# 01_SERIALIZER_V1-0.net
KiCad netlist of a schematic drawn in Altium Designer
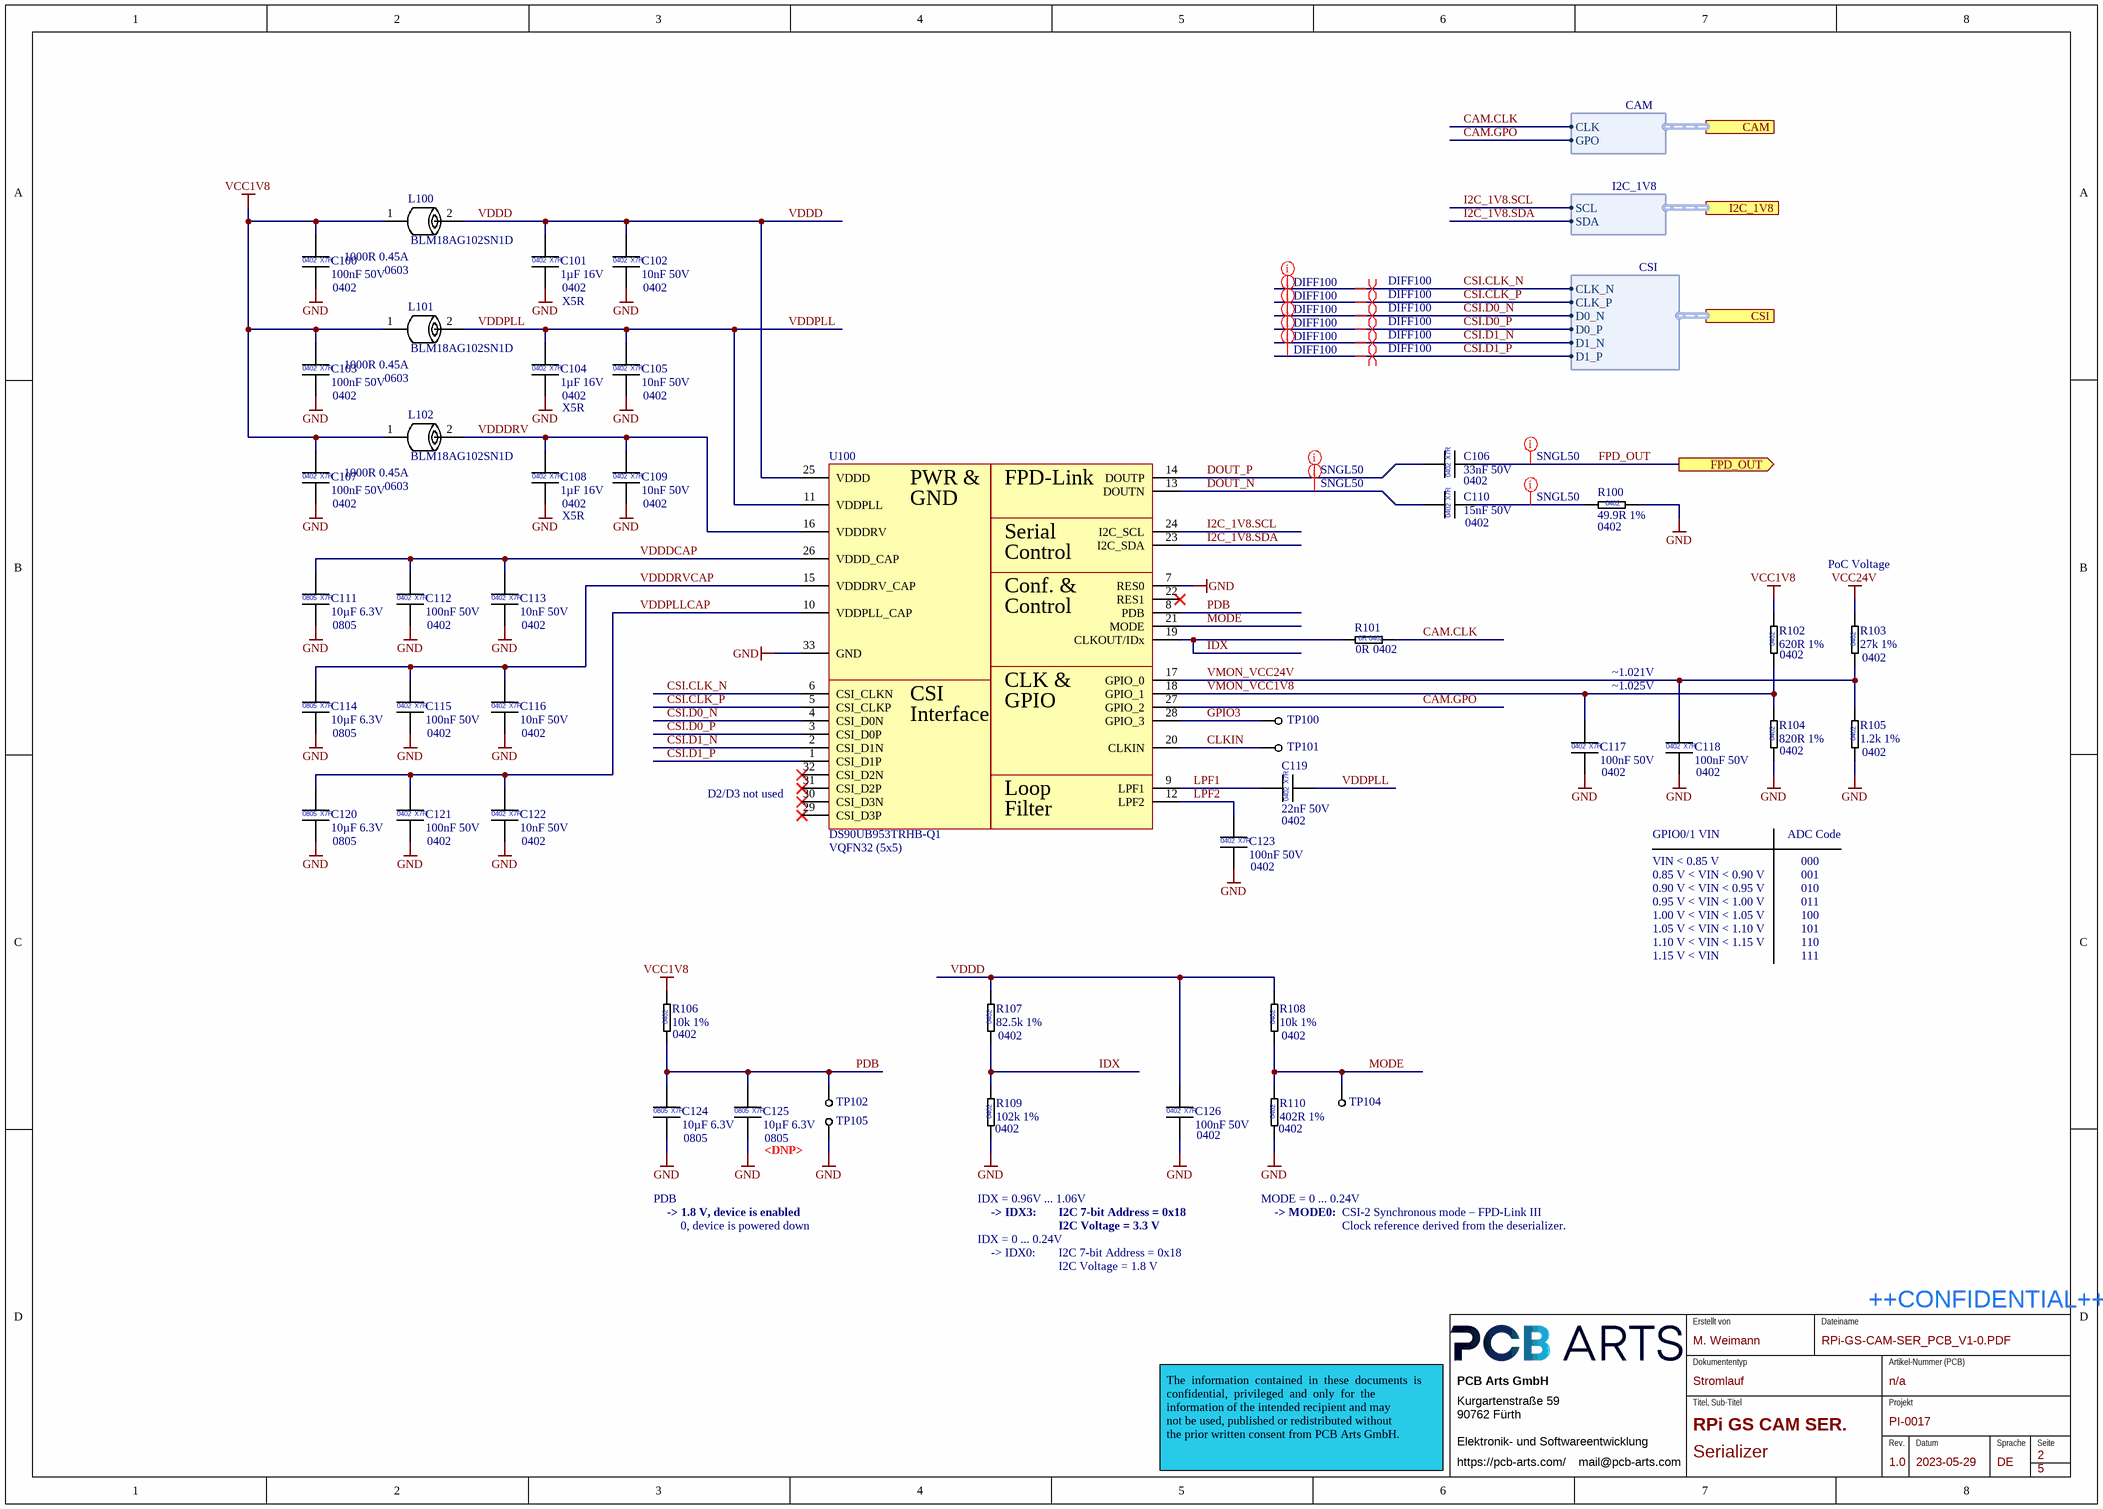
[diagram p0: 01_SERIALIZER_V1-0.SchDoc]

(export (version "E")
  (design (tool "Eeschema 10.0.6"))
  (components
    (comp (ref "C100")
      (value "100nF 50V")
      (footprint "Cap:CAP_0402_L")
      (description "Multilayer Ceramic Capacitors MLCC - SMD/SMT 0402 50VDC")
      (libsource (lib "Cap") (part "CAP_0402_100nF_50V"))
    )
    (comp (ref "C101")
      (value "1µF 16V")
      (footprint "Cap:CAP_0402_L")
      (description "Multilayer Ceramic Capacitors MLCC - SMD/SMT 0402 16VDC")
      (libsource (lib "Cap") (part "CAP_0402_1µF_16V"))
    )
    (comp (ref "C102")
      (value "10nF 50V")
      (footprint "Cap:CAP_0402_L")
      (description "Multilayer Ceramic Capacitors MLCC - SMD/SMT 0402 50VDC")
      (libsource (lib "Cap") (part "CAP_0402_10nF_50V"))
    )
    (comp (ref "C103")
      (value "100nF 50V")
      (footprint "Cap:CAP_0402_L")
      (description "Multilayer Ceramic Capacitors MLCC - SMD/SMT 0402 50VDC")
      (libsource (lib "Cap") (part "CAP_0402_100nF_50V"))
    )
    (comp (ref "C104")
      (value "1µF 16V")
      (footprint "Cap:CAP_0402_L")
      (description "Multilayer Ceramic Capacitors MLCC - SMD/SMT 0402 16VDC")
      (libsource (lib "Cap") (part "CAP_0402_1µF_16V"))
    )
    (comp (ref "C105")
      (value "10nF 50V")
      (footprint "Cap:CAP_0402_L")
      (description "Multilayer Ceramic Capacitors MLCC - SMD/SMT 0402 50VDC")
      (libsource (lib "Cap") (part "CAP_0402_10nF_50V"))
    )
    (comp (ref "C106")
      (value "33nF 50V")
      (footprint "Cap:CAP_0402_L")
      (description "Multilayer Ceramic Capacitors MLCC - SMD/SMT 0402 50VDC")
      (libsource (lib "Cap") (part "CAP_0402_33nF_50V"))
    )
    (comp (ref "C107")
      (value "100nF 50V")
      (footprint "Cap:CAP_0402_L")
      (description "Multilayer Ceramic Capacitors MLCC - SMD/SMT 0402 50VDC")
      (libsource (lib "Cap") (part "CAP_0402_100nF_50V"))
    )
    (comp (ref "C108")
      (value "1µF 16V")
      (footprint "Cap:CAP_0402_L")
      (description "Multilayer Ceramic Capacitors MLCC - SMD/SMT 0402 16VDC")
      (libsource (lib "Cap") (part "CAP_0402_1µF_16V"))
    )
    (comp (ref "C109")
      (value "10nF 50V")
      (footprint "Cap:CAP_0402_L")
      (description "Multilayer Ceramic Capacitors MLCC - SMD/SMT 0402 50VDC")
      (libsource (lib "Cap") (part "CAP_0402_10nF_50V"))
    )
    (comp (ref "C110")
      (value "15nF 50V")
      (footprint "Cap:CAP_0402_L")
      (description "Multilayer Ceramic Capacitors MLCC - SMD/SMT 0402 50VDC")
      (libsource (lib "Cap") (part "CAP_0402_15nF_50V"))
    )
    (comp (ref "C111")
      (value "10µF 6.3V")
      (footprint "Cap:CAP_0805")
      (description "Multilayer Ceramic Capacitors MLCC - SMD/SMT 10 uF 6.3 VDC 10% 0805 X7R")
      (libsource (lib "Cap") (part "CAP_0805_10µF_6.3V_X7R_10%"))
    )
    (comp (ref "C112")
      (value "100nF 50V")
      (footprint "Cap:CAP_0402_L")
      (description "Multilayer Ceramic Capacitors MLCC - SMD/SMT 0402 50VDC")
      (libsource (lib "Cap") (part "CAP_0402_100nF_50V"))
    )
    (comp (ref "C113")
      (value "10nF 50V")
      (footprint "Cap:CAP_0402_L")
      (description "Multilayer Ceramic Capacitors MLCC - SMD/SMT 0402 50VDC")
      (libsource (lib "Cap") (part "CAP_0402_10nF_50V"))
    )
    (comp (ref "C114")
      (value "10µF 6.3V")
      (footprint "Cap:CAP_0805")
      (description "Multilayer Ceramic Capacitors MLCC - SMD/SMT 10 uF 6.3 VDC 10% 0805 X7R")
      (libsource (lib "Cap") (part "CAP_0805_10µF_6.3V_X7R_10%"))
    )
    (comp (ref "C115")
      (value "100nF 50V")
      (footprint "Cap:CAP_0402_L")
      (description "Multilayer Ceramic Capacitors MLCC - SMD/SMT 0402 50VDC")
      (libsource (lib "Cap") (part "CAP_0402_100nF_50V"))
    )
    (comp (ref "C116")
      (value "10nF 50V")
      (footprint "Cap:CAP_0402_L")
      (description "Multilayer Ceramic Capacitors MLCC - SMD/SMT 0402 50VDC")
      (libsource (lib "Cap") (part "CAP_0402_10nF_50V"))
    )
    (comp (ref "C117")
      (value "100nF 50V")
      (footprint "Cap:CAP_0402_L")
      (description "Multilayer Ceramic Capacitors MLCC - SMD/SMT 0402 50VDC")
      (libsource (lib "Cap") (part "CAP_0402_100nF_50V"))
    )
    (comp (ref "C118")
      (value "100nF 50V")
      (footprint "Cap:CAP_0402_L")
      (description "Multilayer Ceramic Capacitors MLCC - SMD/SMT 0402 50VDC")
      (libsource (lib "Cap") (part "CAP_0402_100nF_50V"))
    )
    (comp (ref "C119")
      (value "22nF 50V")
      (footprint "Cap:CAP_0402_L")
      (description "Multilayer Ceramic Capacitors MLCC - SMD/SMT 0402 50VDC")
      (libsource (lib "Cap") (part "CAP_0402_22nF_50V"))
    )
    (comp (ref "C120")
      (value "10µF 6.3V")
      (footprint "Cap:CAP_0805")
      (description "Multilayer Ceramic Capacitors MLCC - SMD/SMT 10 uF 6.3 VDC 10% 0805 X7R")
      (libsource (lib "Cap") (part "CAP_0805_10µF_6.3V_X7R_10%"))
    )
    (comp (ref "C121")
      (value "100nF 50V")
      (footprint "Cap:CAP_0402_L")
      (description "Multilayer Ceramic Capacitors MLCC - SMD/SMT 0402 50VDC")
      (libsource (lib "Cap") (part "CAP_0402_100nF_50V"))
    )
    (comp (ref "C122")
      (value "10nF 50V")
      (footprint "Cap:CAP_0402_L")
      (description "Multilayer Ceramic Capacitors MLCC - SMD/SMT 0402 50VDC")
      (libsource (lib "Cap") (part "CAP_0402_10nF_50V"))
    )
    (comp (ref "C123")
      (value "100nF 50V")
      (footprint "Cap:CAP_0402_L")
      (description "Multilayer Ceramic Capacitors MLCC - SMD/SMT 0402 50VDC")
      (libsource (lib "Cap") (part "CAP_0402_100nF_50V"))
    )
    (comp (ref "C124")
      (value "10µF 6.3V")
      (footprint "Cap:CAP_0805")
      (description "Multilayer Ceramic Capacitors MLCC - SMD/SMT 10 uF 6.3 VDC 10% 0805 X7R")
      (libsource (lib "Cap") (part "CAP_0805_10µF_6.3V_X7R_10%"))
    )
    (comp (ref "C125")
      (value "10µF 6.3V")
      (footprint "Cap:CAP_0805")
      (description "Multilayer Ceramic Capacitors MLCC - SMD/SMT 10 uF 6.3 VDC 10% 0805 X7R")
      (libsource (lib "Cap") (part "CAP_0805_10µF_6.3V_X7R_10%"))
    )
    (comp (ref "C126")
      (value "100nF 50V")
      (footprint "Cap:CAP_0402_L")
      (description "Multilayer Ceramic Capacitors MLCC - SMD/SMT 0402 50VDC")
      (libsource (lib "Cap") (part "CAP_0402_100nF_50V"))
    )
    (comp (ref "L100")
      (value "BLM18AG102SN1D")
      (footprint "L_0603")
      (description "Ferrite Beads BLM18 1000Ohms 450mA 0,5Ohm")
      (libsource (lib "Indc") (part "BLM18AG102SN1D_Ferrite Beads 0603 1000Ohms 450mA"))
    )
    (comp (ref "L101")
      (value "BLM18AG102SN1D")
      (footprint "L_0603")
      (description "Ferrite Beads BLM18 1000Ohms 450mA 0,5Ohm")
      (libsource (lib "Indc") (part "BLM18AG102SN1D_Ferrite Beads 0603 1000Ohms 450mA"))
    )
    (comp (ref "L102")
      (value "BLM18AG102SN1D")
      (footprint "L_0603")
      (description "Ferrite Beads BLM18 1000Ohms 450mA 0,5Ohm")
      (libsource (lib "Indc") (part "BLM18AG102SN1D_Ferrite Beads 0603 1000Ohms 450mA"))
    )
    (comp (ref "R100")
      (value "49.9R 1%")
      (footprint "Res:RES_0402_L")
      (description "Thick Film Resistors - SMD 49.9Ohm 1%")
      (libsource (lib "Res") (part "RES_0402_49.9R_1%"))
    )
    (comp (ref "R101")
      (value "0R Jumper")
      (footprint "Res:RES_0402_L")
      (description "Thick Film Resistors - SMD 0Ohm")
      (libsource (lib "Res") (part "RES_0402_0R Jumper"))
    )
    (comp (ref "R102")
      (value "620R 1%")
      (footprint "Res:RES_0402_L")
      (description "Thick Film Resistors - SMD 1/16watt 620ohms 1%")
      (libsource (lib "Res") (part "RES_0402_620R_1%"))
    )
    (comp (ref "R103")
      (value "27k 1%")
      (footprint "Res:RES_0402_L")
      (description "Thick Film Resistors - SMD 27kOhm 1%")
      (libsource (lib "Res") (part "RES_0402_27k_1%"))
    )
    (comp (ref "R104")
      (value "820R 1%")
      (footprint "Res:RES_0402_L")
      (description "Thick Film Resistors - SMD 1/16watt 820ohms 1%")
      (libsource (lib "Res") (part "RES_0402_820R_1%"))
    )
    (comp (ref "R105")
      (value "1.2k 1%")
      (footprint "Res:RES_0402_L")
      (description "Thick Film Resistors - SMD 1/16watt 1.2Kohms 1%")
      (libsource (lib "Res") (part "RES_0402_1.2k_1%"))
    )
    (comp (ref "R106")
      (value "10k 1%")
      (footprint "Res:RES_0402_L")
      (description "Thick Film Resistors - SMD 10kOhm 1%")
      (libsource (lib "Res") (part "RES_0402_10k_1%"))
    )
    (comp (ref "R107")
      (value "82.5k 1%")
      (footprint "Res:RES_0402_L")
      (description "Thick Film Resistors - SMD 1/16W 82.5Kohms 1%")
      (libsource (lib "Res") (part "RES_0402_82.5k_1%"))
    )
    (comp (ref "R108")
      (value "10k 1%")
      (footprint "Res:RES_0402_L")
      (description "Thick Film Resistors - SMD 10kOhm 1%")
      (libsource (lib "Res") (part "RES_0402_10k_1%"))
    )
    (comp (ref "R109")
      (value "102k 1%")
      (footprint "Res:RES_0402_L")
      (description "Thick Film Resistors - SMD 102KOHM 1/16WATT 1%")
      (libsource (lib "Res") (part "RES_0402_102k_1%"))
    )
    (comp (ref "R110")
      (value "402R 1%")
      (footprint "Res:RES_0402_L")
      (description "Thick Film Resistors - SMD 402Ohms 1/16W 0402 1%")
      (libsource (lib "Res") (part "RES_0402_402R_1%"))
    )
    (comp (ref "TP100")
      (value "Testpoint")
      (footprint "Electro_mech:Testpoint 0.8mm")
      (description "Testpoint 0.8mm")
      (libsource (lib "Electro_Mech") (part "Testpoint 0.8mm"))
    )
    (comp (ref "TP101")
      (value "Testpoint")
      (footprint "Electro_mech:Testpoint 0.8mm")
      (description "Testpoint 0.8mm")
      (libsource (lib "Electro_Mech") (part "Testpoint 0.8mm"))
    )
    (comp (ref "TP102")
      (value "Testpoint")
      (footprint "Electro_mech:Testpoint 0.8mm")
      (description "Testpoint 0.8mm")
      (libsource (lib "Electro_Mech") (part "Testpoint 0.8mm"))
    )
    (comp (ref "TP104")
      (value "Testpoint")
      (footprint "Electro_mech:Testpoint 0.8mm")
      (description "Testpoint 0.8mm")
      (libsource (lib "Electro_Mech") (part "Testpoint 0.8mm"))
    )
    (comp (ref "TP105")
      (value "Testpoint")
      (footprint "Electro_mech:Testpoint 0.8mm")
      (description "Testpoint 0.8mm")
      (libsource (lib "Electro_Mech") (part "Testpoint 0.8mm"))
    )
    (comp (ref "U100")
      (value "DS90UB953TRHB-Q1")
      (footprint "Digital:VQFN50P500X500X100-33N")
      (libsource (lib "Digital") (part "DS90UB953TRHBTQ1_Serialiser CSI-2 Interface"))
    )
  )
  (nets
    (net (code "4") (name "/CAM.CLK") (class "Default")
      (node (ref "R101") (pin "2") (pinfunction "2_2") (pintype "passive"))
    )
    (net (code "5") (name "/CAM.GPO") (class "Default")
      (node (ref "U100") (pin "27") (pinfunction "GPIO_2_27") (pintype "passive"))
    )
    (net (code "6") (name "/CLKIN") (class "Default")
      (node (ref "TP101") (pin "1") (pinfunction "GND_1") (pintype "passive"))
      (node (ref "U100") (pin "20") (pinfunction "CLKIN_20") (pintype "passive"))
    )
    (net (code "7") (name "/CSI.CLK_N") (class "Default")
      (node (ref "U100") (pin "6") (pinfunction "CSI_CLKN_6") (pintype "passive"))
    )
    (net (code "8") (name "/CSI.CLK_P") (class "Default")
      (node (ref "U100") (pin "5") (pinfunction "CSI_CLKP_5") (pintype "passive"))
    )
    (net (code "9") (name "/CSI.D0_N") (class "Default")
      (node (ref "U100") (pin "4") (pinfunction "CSI_D0N_4") (pintype "passive"))
    )
    (net (code "10") (name "/CSI.D0_P") (class "Default")
      (node (ref "U100") (pin "3") (pinfunction "CSI_D0P_3") (pintype "passive"))
    )
    (net (code "11") (name "/CSI.D1_N") (class "Default")
      (node (ref "U100") (pin "2") (pinfunction "CSI_D1N_2") (pintype "passive"))
    )
    (net (code "12") (name "/CSI.D1_P") (class "Default")
      (node (ref "U100") (pin "1") (pinfunction "CSI_D1P_1") (pintype "passive"))
    )
    (net (code "13") (name "/DOUT_N") (class "Default")
      (node (ref "C110") (pin "1") (pinfunction "1_1") (pintype "passive"))
      (node (ref "U100") (pin "13") (pinfunction "DOUTN_13") (pintype "passive"))
    )
    (net (code "14") (name "/DOUT_P") (class "Default")
      (node (ref "C106") (pin "1") (pinfunction "1_1") (pintype "passive"))
      (node (ref "U100") (pin "14") (pinfunction "DOUTP_14") (pintype "passive"))
    )
    (net (code "15") (name "/FPD_OUT") (class "Default")
      (node (ref "C106") (pin "2") (pinfunction "2_2") (pintype "passive"))
    )
    (net (code "16") (name "/GPIO3") (class "Default")
      (node (ref "TP100") (pin "1") (pinfunction "GND_1") (pintype "passive"))
      (node (ref "U100") (pin "28") (pinfunction "GPIO_3_28") (pintype "passive"))
    )
    (net (code "17") (name "/I2C_1V8.SCL") (class "Default")
      (node (ref "U100") (pin "24") (pinfunction "I2C_SCL_24") (pintype "passive"))
    )
    (net (code "18") (name "/I2C_1V8.SDA") (class "Default")
      (node (ref "U100") (pin "23") (pinfunction "I2C_SDA_23") (pintype "passive"))
    )
    (net (code "19") (name "/IDX") (class "Default")
      (node (ref "R101") (pin "1") (pinfunction "1_1") (pintype "passive"))
      (node (ref "R107") (pin "1") (pinfunction "1_1") (pintype "passive"))
      (node (ref "R109") (pin "2") (pinfunction "2_2") (pintype "passive"))
      (node (ref "U100") (pin "19") (pinfunction "CLKOUT/IDx_19") (pintype "passive"))
    )
    (net (code "20") (name "/LPF1") (class "Default")
      (node (ref "C119") (pin "1") (pinfunction "1_1") (pintype "passive"))
      (node (ref "U100") (pin "9") (pinfunction "LPF1_9") (pintype "passive"))
    )
    (net (code "21") (name "/LPF2") (class "Default")
      (node (ref "C123") (pin "1") (pinfunction "1_1") (pintype "passive"))
      (node (ref "U100") (pin "12") (pinfunction "LPF2_12") (pintype "passive"))
    )
    (net (code "22") (name "/MODE") (class "Default")
      (node (ref "R108") (pin "1") (pinfunction "1_1") (pintype "passive"))
      (node (ref "R110") (pin "2") (pinfunction "2_2") (pintype "passive"))
      (node (ref "TP104") (pin "1") (pinfunction "GND_1") (pintype "passive"))
      (node (ref "U100") (pin "21") (pinfunction "MODE_21") (pintype "passive"))
    )
    (net (code "23") (name "/PDB") (class "Default")
      (node (ref "C124") (pin "1") (pinfunction "1_1") (pintype "passive"))
      (node (ref "C125") (pin "1") (pinfunction "1_1") (pintype "passive"))
      (node (ref "R106") (pin "1") (pinfunction "1_1") (pintype "passive"))
      (node (ref "TP102") (pin "1") (pinfunction "GND_1") (pintype "passive"))
      (node (ref "U100") (pin "8") (pinfunction "PDB_8") (pintype "passive"))
    )
    (net (code "24") (name "/VDDD") (class "Default")
      (node (ref "C101") (pin "1") (pinfunction "1_1") (pintype "passive"))
      (node (ref "C102") (pin "1") (pinfunction "1_1") (pintype "passive"))
      (node (ref "C126") (pin "1") (pinfunction "1_1") (pintype "passive"))
      (node (ref "L100") (pin "2") (pinfunction "2_2") (pintype "passive"))
      (node (ref "R107") (pin "2") (pinfunction "2_2") (pintype "passive"))
      (node (ref "R108") (pin "2") (pinfunction "2_2") (pintype "passive"))
      (node (ref "U100") (pin "25") (pinfunction "VDDD_25") (pintype "passive"))
    )
    (net (code "25") (name "/VDDDCAP") (class "Default")
      (node (ref "C111") (pin "1") (pinfunction "1_1") (pintype "passive"))
      (node (ref "C112") (pin "1") (pinfunction "1_1") (pintype "passive"))
      (node (ref "C113") (pin "1") (pinfunction "1_1") (pintype "passive"))
      (node (ref "U100") (pin "26") (pinfunction "VDDD_CAP_26") (pintype "passive"))
    )
    (net (code "26") (name "/VDDDRV") (class "Default")
      (node (ref "C108") (pin "1") (pinfunction "1_1") (pintype "passive"))
      (node (ref "C109") (pin "1") (pinfunction "1_1") (pintype "passive"))
      (node (ref "L102") (pin "2") (pinfunction "2_2") (pintype "passive"))
      (node (ref "U100") (pin "16") (pinfunction "VDDDRV_16") (pintype "passive"))
    )
    (net (code "27") (name "/VDDDRVCAP") (class "Default")
      (node (ref "C114") (pin "1") (pinfunction "1_1") (pintype "passive"))
      (node (ref "C115") (pin "1") (pinfunction "1_1") (pintype "passive"))
      (node (ref "C116") (pin "1") (pinfunction "1_1") (pintype "passive"))
      (node (ref "U100") (pin "15") (pinfunction "VDDDRV_CAP_15") (pintype "passive"))
    )
    (net (code "28") (name "/VDDPLL") (class "Default")
      (node (ref "C104") (pin "1") (pinfunction "1_1") (pintype "passive"))
      (node (ref "C105") (pin "1") (pinfunction "1_1") (pintype "passive"))
      (node (ref "C119") (pin "2") (pinfunction "2_2") (pintype "passive"))
      (node (ref "L101") (pin "2") (pinfunction "2_2") (pintype "passive"))
      (node (ref "U100") (pin "11") (pinfunction "VDDPLL_11") (pintype "passive"))
    )
    (net (code "29") (name "/VDDPLLCAP") (class "Default")
      (node (ref "C120") (pin "1") (pinfunction "1_1") (pintype "passive"))
      (node (ref "C121") (pin "1") (pinfunction "1_1") (pintype "passive"))
      (node (ref "C122") (pin "1") (pinfunction "1_1") (pintype "passive"))
      (node (ref "U100") (pin "10") (pinfunction "VDDPLL_CAP_10") (pintype "passive"))
    )
    (net (code "30") (name "/VMON_VCC1V8") (class "Default")
      (node (ref "C117") (pin "1") (pinfunction "1_1") (pintype "passive"))
      (node (ref "R102") (pin "1") (pinfunction "1_1") (pintype "passive"))
      (node (ref "R104") (pin "2") (pinfunction "2_2") (pintype "passive"))
      (node (ref "U100") (pin "18") (pinfunction "GPIO_1_18") (pintype "passive"))
    )
    (net (code "31") (name "/VMON_VCC24V") (class "Default")
      (node (ref "C118") (pin "1") (pinfunction "1_1") (pintype "passive"))
      (node (ref "R103") (pin "1") (pinfunction "1_1") (pintype "passive"))
      (node (ref "R105") (pin "2") (pinfunction "2_2") (pintype "passive"))
      (node (ref "U100") (pin "17") (pinfunction "GPIO_0_17") (pintype "passive"))
    )
    (net (code "35") (name "GND") (class "Default")
      (node (ref "C100") (pin "2") (pinfunction "2_2") (pintype "passive"))
      (node (ref "C101") (pin "2") (pinfunction "2_2") (pintype "passive"))
      (node (ref "C102") (pin "2") (pinfunction "2_2") (pintype "passive"))
      (node (ref "C103") (pin "2") (pinfunction "2_2") (pintype "passive"))
      (node (ref "C104") (pin "2") (pinfunction "2_2") (pintype "passive"))
      (node (ref "C105") (pin "2") (pinfunction "2_2") (pintype "passive"))
      (node (ref "C107") (pin "2") (pinfunction "2_2") (pintype "passive"))
      (node (ref "C108") (pin "2") (pinfunction "2_2") (pintype "passive"))
      (node (ref "C109") (pin "2") (pinfunction "2_2") (pintype "passive"))
      (node (ref "C111") (pin "2") (pinfunction "2_2") (pintype "passive"))
      (node (ref "C112") (pin "2") (pinfunction "2_2") (pintype "passive"))
      (node (ref "C113") (pin "2") (pinfunction "2_2") (pintype "passive"))
      (node (ref "C114") (pin "2") (pinfunction "2_2") (pintype "passive"))
      (node (ref "C115") (pin "2") (pinfunction "2_2") (pintype "passive"))
      (node (ref "C116") (pin "2") (pinfunction "2_2") (pintype "passive"))
      (node (ref "C117") (pin "2") (pinfunction "2_2") (pintype "passive"))
      (node (ref "C118") (pin "2") (pinfunction "2_2") (pintype "passive"))
      (node (ref "C120") (pin "2") (pinfunction "2_2") (pintype "passive"))
      (node (ref "C121") (pin "2") (pinfunction "2_2") (pintype "passive"))
      (node (ref "C122") (pin "2") (pinfunction "2_2") (pintype "passive"))
      (node (ref "C123") (pin "2") (pinfunction "2_2") (pintype "passive"))
      (node (ref "C124") (pin "2") (pinfunction "2_2") (pintype "passive"))
      (node (ref "C125") (pin "2") (pinfunction "2_2") (pintype "passive"))
      (node (ref "C126") (pin "2") (pinfunction "2_2") (pintype "passive"))
      (node (ref "R100") (pin "2") (pinfunction "2_2") (pintype "passive"))
      (node (ref "R104") (pin "1") (pinfunction "1_1") (pintype "passive"))
      (node (ref "R105") (pin "1") (pinfunction "1_1") (pintype "passive"))
      (node (ref "R109") (pin "1") (pinfunction "1_1") (pintype "passive"))
      (node (ref "R110") (pin "1") (pinfunction "1_1") (pintype "passive"))
      (node (ref "TP105") (pin "1") (pinfunction "GND_1") (pintype "passive"))
      (node (ref "U100") (pin "33") (pinfunction "GND_33") (pintype "passive"))
      (node (ref "U100") (pin "7") (pinfunction "RES0_7") (pintype "passive"))
    )
    (net (code "36") (name "Net-(C110-Pad2)") (class "Default")
      (node (ref "C110") (pin "2") (pinfunction "2_2") (pintype "passive"))
      (node (ref "R100") (pin "1") (pinfunction "1_1") (pintype "passive"))
    )
    (net (code "37") (name "VCC1V8") (class "Default")
      (node (ref "C100") (pin "1") (pinfunction "1_1") (pintype "passive"))
      (node (ref "C103") (pin "1") (pinfunction "1_1") (pintype "passive"))
      (node (ref "C107") (pin "1") (pinfunction "1_1") (pintype "passive"))
      (node (ref "L100") (pin "1") (pinfunction "1_1") (pintype "passive"))
      (node (ref "L101") (pin "1") (pinfunction "1_1") (pintype "passive"))
      (node (ref "L102") (pin "1") (pinfunction "1_1") (pintype "passive"))
      (node (ref "R102") (pin "2") (pinfunction "2_2") (pintype "passive"))
      (node (ref "R106") (pin "2") (pinfunction "2_2") (pintype "passive"))
    )
    (net (code "38") (name "VCC24V") (class "Default")
      (node (ref "R103") (pin "2") (pinfunction "2_2") (pintype "passive"))
    )
    (net (code "39") (name "unconnected-(U100-CSI_D2N-Pad32)") (class "Default")
      (node (ref "U100") (pin "32") (pinfunction "CSI_D2N_32") (pintype "passive+no_connect"))
    )
    (net (code "40") (name "unconnected-(U100-CSI_D2P-Pad31)") (class "Default")
      (node (ref "U100") (pin "31") (pinfunction "CSI_D2P_31") (pintype "passive+no_connect"))
    )
    (net (code "41") (name "unconnected-(U100-CSI_D3N-Pad30)") (class "Default")
      (node (ref "U100") (pin "30") (pinfunction "CSI_D3N_30") (pintype "passive+no_connect"))
    )
    (net (code "42") (name "unconnected-(U100-CSI_D3P-Pad29)") (class "Default")
      (node (ref "U100") (pin "29") (pinfunction "CSI_D3P_29") (pintype "passive+no_connect"))
    )
    (net (code "43") (name "unconnected-(U100-RES1-Pad22)") (class "Default")
      (node (ref "U100") (pin "22") (pinfunction "RES1_22") (pintype "passive+no_connect"))
    )
  )
)
